# FlowSensor.net
KiCad netlist of a schematic drawn in EAGLE
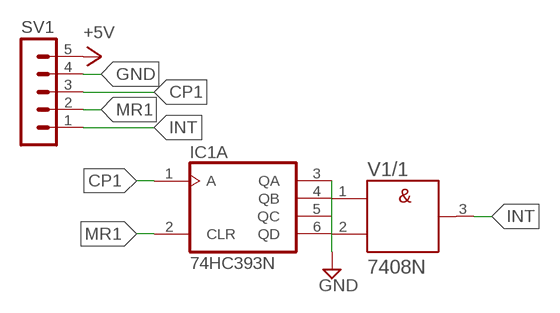
[diagram p0: schematic, sheet 1]

(export (version "E")
  (design (tool "Eeschema 10.0.6"))
  (components
    (comp (ref "IC1")
      (value "74HC393N")
      (footprint "eagle-import:DIL14")
      (libsource (lib "eagle-import") (part "74393NHC"))
    )
    (comp (ref "SV1")
      (value "MA05-1")
      (footprint "eagle-import:MA05-1")
      (libsource (lib "eagle-import") (part "MA05-1"))
    )
    (comp (ref "V1")
      (value "7408N")
      (footprint "eagle-import:DIL14")
      (libsource (lib "eagle-import") (part "7408N"))
    )
  )
  (nets
    (net (code "1") (name "+5V") (class "Default")
      (node (ref "SV1") (pin "5") (pinfunction "5_5") (pintype "passive"))
    )
    (net (code "2") (name "CP1") (class "Default")
      (node (ref "IC1") (pin "1") (pinfunction "A_1") (pintype "input"))
      (node (ref "SV1") (pin "3") (pinfunction "3_3") (pintype "passive"))
    )
    (net (code "3") (name "GND") (class "Default")
      (node (ref "IC1") (pin "3") (pinfunction "QA_3") (pintype "output"))
      (node (ref "IC1") (pin "5") (pinfunction "QC_5") (pintype "output"))
      (node (ref "SV1") (pin "4") (pinfunction "4_4") (pintype "passive"))
    )
    (net (code "4") (name "INT") (class "Default")
      (node (ref "SV1") (pin "1") (pinfunction "1_1") (pintype "passive"))
      (node (ref "V1") (pin "3") (pinfunction "Y_3") (pintype "output"))
    )
    (net (code "5") (name "MR1") (class "Default")
      (node (ref "IC1") (pin "2") (pinfunction "CLR_2") (pintype "input"))
      (node (ref "SV1") (pin "2") (pinfunction "2_2") (pintype "passive"))
    )
    (net (code "6") (name "Net-(IC1A-QB)") (class "Default")
      (node (ref "IC1") (pin "4") (pinfunction "QB_4") (pintype "output"))
      (node (ref "V1") (pin "1") (pinfunction "A_1") (pintype "input"))
    )
    (net (code "7") (name "Net-(IC1A-QD)") (class "Default")
      (node (ref "IC1") (pin "6") (pinfunction "QD_6") (pintype "output"))
      (node (ref "V1") (pin "2") (pinfunction "B_2") (pintype "input"))
    )
  )
)
